# shkabara_motherboard.net
KiCad netlist of a schematic drawn in Altium Designer
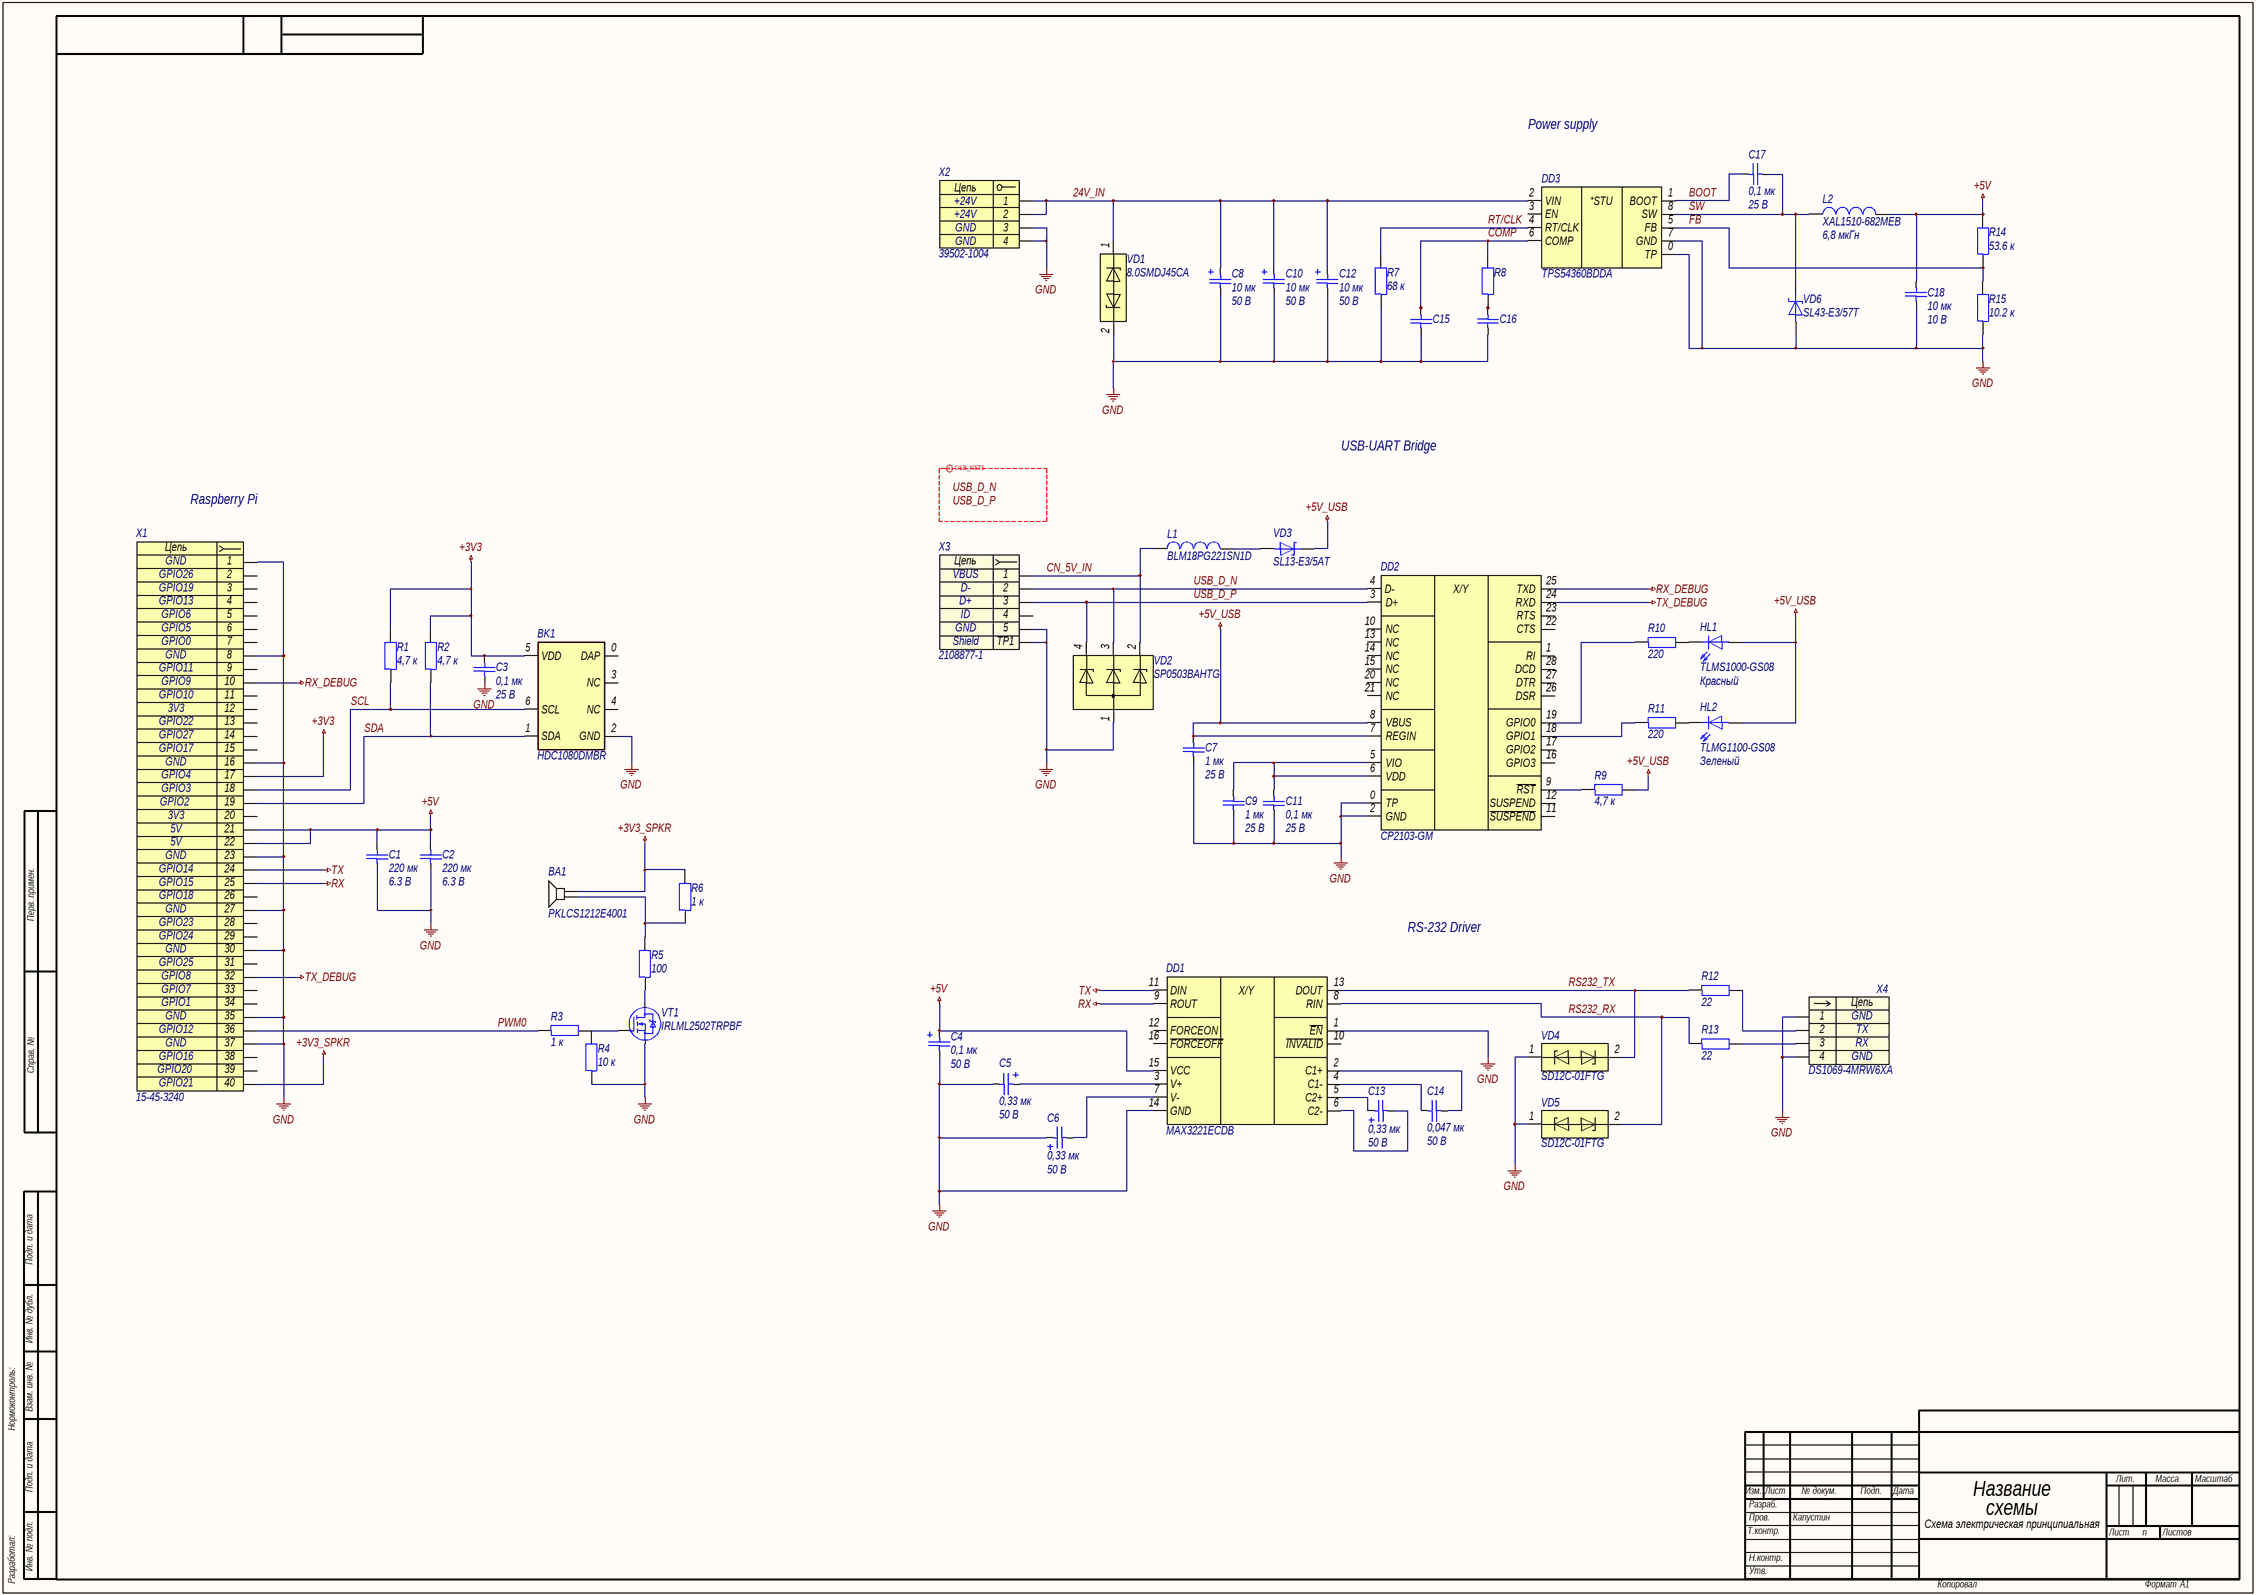
[diagram p0: shkabara_motherboard.SchDoc]

(export (version "E")
  (design (tool "Eeschema 10.0.6"))
  (components
    (comp (ref "BA1")
      (value "PKLCS1212E4001")
      (footprint "PKLCS1212E4001")
      (description "Piezoelectric Sounders External Drive SMD Type")
      (libsource (lib "PKLCS1212E4001") (part "PKLCS1212E4001"))
    )
    (comp (ref "BK1")
      (value "HDC1080DMBR")
      (footprint "PSON100P300X80_HS-7N")
      (description "HDC1080 Low Power, High Accuracy Digital Humidity Sensor with Temperature Sensor")
      (libsource (lib "HDC1080") (part "HDC1080"))
    )
    (comp (ref "C1")
      (value "220 мк")
      (footprint "C1210")
      (description "=Описание")
      (fields (field (name "НАПРЯЖЕНИЕ") "6.3 В"))
      (libsource (lib "Database_Students") (part "CAPACITOR-NONPOLAR"))
    )
    (comp (ref "C2")
      (value "220 мк")
      (footprint "C1210")
      (description "=Описание")
      (fields (field (name "НАПРЯЖЕНИЕ") "6.3 В"))
      (libsource (lib "Database_Students") (part "CAPACITOR-NONPOLAR"))
    )
    (comp (ref "C3")
      (value "0,1 мк")
      (footprint "C0402")
      (description "=Описание")
      (fields (field (name "НАПРЯЖЕНИЕ") "25 В"))
      (libsource (lib "Database_Students") (part "CAPACITOR-NONPOLAR"))
    )
    (comp (ref "C4")
      (value "0,1 мк")
      (footprint "C3216-18")
      (description "=Описание")
      (fields (field (name "НАПРЯЖЕНИЕ") "50 В"))
      (libsource (lib "Database_Students") (part "CAPACITOR-POLAR"))
    )
    (comp (ref "C5")
      (value "0,33 мк")
      (footprint "C3528-21")
      (description "=Описание")
      (fields (field (name "НАПРЯЖЕНИЕ") "50 В"))
      (libsource (lib "Database_Students") (part "CAPACITOR-POLAR"))
    )
    (comp (ref "C6")
      (value "0,33 мк")
      (footprint "C3528-21")
      (description "=Описание")
      (fields (field (name "НАПРЯЖЕНИЕ") "50 В"))
      (libsource (lib "Database_Students") (part "CAPACITOR-POLAR"))
    )
    (comp (ref "C7")
      (value "1 мк")
      (footprint "C0603")
      (description "=Описание")
      (fields (field (name "НАПРЯЖЕНИЕ") "25 В"))
      (libsource (lib "Database_Students") (part "CAPACITOR-NONPOLAR"))
    )
    (comp (ref "C8")
      (value "10 мк")
      (footprint "C7343-43")
      (description "=Описание")
      (fields (field (name "НАПРЯЖЕНИЕ") "50 В"))
      (libsource (lib "Database_Students") (part "CAPACITOR-POLAR"))
    )
    (comp (ref "C9")
      (value "1 мк")
      (footprint "C0603")
      (description "=Описание")
      (fields (field (name "НАПРЯЖЕНИЕ") "25 В"))
      (libsource (lib "Database_Students") (part "CAPACITOR-NONPOLAR"))
    )
    (comp (ref "C10")
      (value "10 мк")
      (footprint "C7343-43")
      (description "=Описание")
      (fields (field (name "НАПРЯЖЕНИЕ") "50 В"))
      (libsource (lib "Database_Students") (part "CAPACITOR-POLAR"))
    )
    (comp (ref "C11")
      (value "0,1 мк")
      (footprint "C0603")
      (description "=Описание")
      (fields (field (name "НАПРЯЖЕНИЕ") "25 В"))
      (libsource (lib "Database_Students") (part "CAPACITOR-NONPOLAR"))
    )
    (comp (ref "C12")
      (value "10 мк")
      (footprint "C7343-43")
      (description "=Описание")
      (fields (field (name "НАПРЯЖЕНИЕ") "50 В"))
      (libsource (lib "Database_Students") (part "CAPACITOR-POLAR"))
    )
    (comp (ref "C13")
      (value "0,33 мк")
      (footprint "C3528-21")
      (description "=Описание")
      (fields (field (name "НАПРЯЖЕНИЕ") "50 В"))
      (libsource (lib "Database_Students") (part "CAPACITOR-POLAR"))
    )
    (comp (ref "C14")
      (value "0,047 мк")
      (footprint "C0603")
      (description "=Описание")
      (fields (field (name "НАПРЯЖЕНИЕ") "50 В"))
      (libsource (lib "Database_Students") (part "CAPACITOR-NONPOLAR"))
    )
    (comp (ref "C15")
      (value "1000")
      (footprint "C0603")
      (description "=Описание")
      (libsource (lib "Database_Students") (part "CAPACITOR-NONPOLAR"))
    )
    (comp (ref "C16")
      (value "0,01 мк")
      (footprint "C0603")
      (description "=Описание")
      (libsource (lib "Database_Students") (part "CAPACITOR-NONPOLAR"))
    )
    (comp (ref "C17")
      (value "0,1 мк")
      (footprint "C0402")
      (description "=Описание")
      (fields (field (name "НАПРЯЖЕНИЕ") "25 В"))
      (libsource (lib "Database_Students") (part "CAPACITOR-NONPOLAR"))
    )
    (comp (ref "C18")
      (value "10 мк")
      (footprint "C0805")
      (description "=Описание")
      (fields (field (name "НАПРЯЖЕНИЕ") "10 В"))
      (libsource (lib "Database_Students") (part "CAPACITOR-NONPOLAR"))
    )
    (comp (ref "DD1")
      (value "MAX3221ECDB")
      (footprint "SSOP-16-P65-620X530X200-L75X30")
      (description "=Описание")
      (libsource (lib "Database_Students") (part "MAX3221ECDB"))
    )
    (comp (ref "DD2")
      (value "CP2103-GM")
      (footprint "QFN-28-P50-500X500X100-L55X25-T315X315")
      (description "=Описание")
      (libsource (lib "Database_Students") (part "CP2103-GM"))
    )
    (comp (ref "DD3")
      (value "TPS54360BDDA")
      (footprint "HSOIC-8-P127-490X390X170-L84X41-T310X240")
      (description "=Описание")
      (libsource (lib "Database_Students") (part "TPS54360BDDA"))
    )
    (comp (ref "HL1")
      (value "TLMS1000-GS08")
      (footprint "HL0603")
      (description "=Описание")
      (fields (field (name "ЦВЕТ") "Красный"))
      (libsource (lib "Database_Students") (part "LED-COMMON"))
    )
    (comp (ref "HL2")
      (value "TLMG1100-GS08")
      (footprint "HL0603")
      (description "=Описание")
      (fields (field (name "ЦВЕТ") "Зеленый"))
      (libsource (lib "Database_Students") (part "LED-COMMON"))
    )
    (comp (ref "L1")
      (value "BLM18PG221SN1D")
      (footprint "BLM-2-0603")
      (description "=Описание")
      (libsource (lib "Database_Students") (part "FERRITE-BEAD"))
    )
    (comp (ref "L2")
      (value "XAL1510-682MEB")
      (footprint "XAL-2-1620X1520X1000")
      (description "=Описание")
      (fields (field (name "ИНДУКТИВНОСТЬ") "6,8 мкГн"))
      (libsource (lib "Database_Students") (part "INDUCTOR-COMMON"))
    )
    (comp (ref "R1")
      (value "4,7 к")
      (footprint "R0603")
      (description "=Описание")
      (libsource (lib "Database_Students") (part "RESISTOR-COMMON"))
    )
    (comp (ref "R2")
      (value "4,7 к")
      (footprint "R0603")
      (description "=Описание")
      (libsource (lib "Database_Students") (part "RESISTOR-COMMON"))
    )
    (comp (ref "R3")
      (value "1 к")
      (footprint "R0603")
      (description "=Описание")
      (libsource (lib "Database_Students") (part "RESISTOR-COMMON"))
    )
    (comp (ref "R4")
      (value "10 к")
      (footprint "R0603")
      (description "=Описание")
      (libsource (lib "Database_Students") (part "RESISTOR-COMMON"))
    )
    (comp (ref "R5")
      (value "100")
      (footprint "R0603")
      (description "=Описание")
      (libsource (lib "Database_Students") (part "RESISTOR-COMMON"))
    )
    (comp (ref "R6")
      (value "1 к")
      (footprint "R0603")
      (description "=Описание")
      (libsource (lib "Database_Students") (part "RESISTOR-COMMON"))
    )
    (comp (ref "R7")
      (value "68 к")
      (footprint "R0603")
      (description "=Описание")
      (libsource (lib "Database_Students") (part "RESISTOR-COMMON"))
    )
    (comp (ref "R8")
      (value "3,3 к")
      (footprint "R0603")
      (description "=Описание")
      (libsource (lib "Database_Students") (part "RESISTOR-COMMON"))
    )
    (comp (ref "R9")
      (value "4,7 к")
      (footprint "R0603")
      (description "=Описание")
      (libsource (lib "Database_Students") (part "RESISTOR-COMMON"))
    )
    (comp (ref "R10")
      (value "220")
      (footprint "R0603")
      (description "=Описание")
      (libsource (lib "Database_Students") (part "RESISTOR-COMMON"))
    )
    (comp (ref "R11")
      (value "220")
      (footprint "R0603")
      (description "=Описание")
      (libsource (lib "Database_Students") (part "RESISTOR-COMMON"))
    )
    (comp (ref "R12")
      (value "22")
      (footprint "R0603")
      (description "=Описание")
      (libsource (lib "Database_Students") (part "RESISTOR-COMMON"))
    )
    (comp (ref "R13")
      (value "22")
      (footprint "R0603")
      (description "=Описание")
      (libsource (lib "Database_Students") (part "RESISTOR-COMMON"))
    )
    (comp (ref "R14")
      (value "53.6 к")
      (footprint "R1218")
      (description "=Описание")
      (libsource (lib "Database_Students") (part "RESISTOR-COMMON"))
    )
    (comp (ref "R15")
      (value "10.2 к")
      (footprint "R1218")
      (description "=Описание")
      (libsource (lib "Database_Students") (part "RESISTOR-COMMON"))
    )
    (comp (ref "VD1")
      (value "8.0SMDJ45CA")
      (footprint "DO-214AB-790X590X262")
      (description "=Описание")
      (libsource (lib "") (part "ZENER-BI-DIRECTIONAL_1"))
    )
    (comp (ref "VD2")
      (value "SP0503BAHTG")
      (footprint "SOT-143-4-P190-292X237X122")
      (description "=Описание")
      (libsource (lib "Database_Students") (part "SP0503BAHTG"))
    )
    (comp (ref "VD3")
      (value "SL13-E3/5AT")
      (footprint "DO-214AC-510X270X229")
      (description "=Описание")
      (libsource (lib "Database_Students") (part "DIODE-SCHOTTKY"))
    )
    (comp (ref "VD4")
      (value "SD12C-01FTG")
      (footprint "SOD-323-257X130X114")
      (description "=Описание")
      (libsource (lib "Database_Students") (part "ZENER-BI-DIRECTIONAL"))
    )
    (comp (ref "VD5")
      (value "SD12C-01FTG")
      (footprint "SOD-323-257X130X114")
      (description "=Описание")
      (libsource (lib "Database_Students") (part "ZENER-BI-DIRECTIONAL"))
    )
    (comp (ref "VD6")
      (value "SL43-E3/57T")
      (footprint "DO-214AB-790X590X262")
      (description "=Описание")
      (libsource (lib "Database_Students") (part "DIODE-SCHOTTKY"))
    )
    (comp (ref "VT1")
      (value "IRLML2502TRPBF")
      (footprint "SOT-23-3-P95-292X237X112")
      (description "=Описание")
      (libsource (lib "Database_Students") (part "MOSFET-N-DIODE-SCHOTTKY"))
    )
    (comp (ref "X1")
      (value "15-45-3240")
      (footprint "15-45-3240")
      (description "=Описание")
      (libsource (lib "Database_Students") (part "HEADER-40-SCT"))
    )
    (comp (ref "X2")
      (value "39502-1004")
      (footprint "39502-1004")
      (description "=Описание")
      (libsource (lib "Database_Students") (part "HEADER-4-TRM"))
    )
    (comp (ref "X3")
      (value "2108877-1")
      (footprint "2108877-1")
      (description "=Описание")
      (libsource (lib "Database_Students") (part "HEADER-5-TP1-SCT"))
    )
    (comp (ref "X4")
      (value "DS1069-4MRW6XA")
      (footprint "DS1069-4MRW6XA")
      (description "=Описание")
      (libsource (lib "Database_Students") (part "HEADER-4-PLG"))
    )
  )
  (nets
    (net (code "1") (name "+3V3") (class "Default")
      (node (ref "BK1") (pin "5") (pinfunction "VDD_5") (pintype "passive"))
      (node (ref "C3") (pin "1") (pinfunction "1_1") (pintype "passive"))
      (node (ref "R1") (pin "2") (pinfunction "2_2") (pintype "passive"))
      (node (ref "R2") (pin "2") (pinfunction "2_2") (pintype "passive"))
      (node (ref "X1") (pin "17") (pinfunction "17_17") (pintype "passive"))
    )
    (net (code "2") (name "+3V3_SPKR") (class "Default")
      (node (ref "BA1") (pin "2") (pinfunction "2_2") (pintype "passive"))
      (node (ref "R6") (pin "2") (pinfunction "2_2") (pintype "passive"))
      (node (ref "X1") (pin "40") (pinfunction "40_40") (pintype "passive"))
    )
    (net (code "3") (name "+5V") (class "Default")
      (node (ref "C1") (pin "1") (pinfunction "1_1") (pintype "passive"))
      (node (ref "C18") (pin "1") (pinfunction "1_1") (pintype "passive"))
      (node (ref "C2") (pin "1") (pinfunction "1_1") (pintype "passive"))
      (node (ref "C4") (pin "1") (pinfunction "1_1") (pintype "passive"))
      (node (ref "DD1") (pin "15") (pinfunction "VCC_15") (pintype "passive"))
      (node (ref "L2") (pin "2") (pinfunction "2_2") (pintype "passive"))
      (node (ref "R14") (pin "2") (pinfunction "2_2") (pintype "passive"))
      (node (ref "X1") (pin "21") (pinfunction "21_21") (pintype "passive"))
      (node (ref "X1") (pin "22") (pinfunction "22_22") (pintype "passive"))
    )
    (net (code "4") (name "+5V_USB") (class "Default")
      (node (ref "C7") (pin "1") (pinfunction "1_1") (pintype "passive"))
      (node (ref "DD2") (pin "7") (pinfunction "REGIN_7") (pintype "passive"))
      (node (ref "DD2") (pin "8") (pinfunction "VBUS_8") (pintype "passive"))
      (node (ref "HL1") (pin "2") (pinfunction "2_2") (pintype "passive"))
      (node (ref "HL2") (pin "2") (pinfunction "2_2") (pintype "passive"))
      (node (ref "R9") (pin "2") (pinfunction "2_2") (pintype "passive"))
      (node (ref "VD3") (pin "1") (pinfunction "1_1") (pintype "passive"))
    )
    (net (code "5") (name "/24V_IN") (class "Default")
      (node (ref "C10") (pin "1") (pinfunction "1_1") (pintype "passive"))
      (node (ref "C12") (pin "1") (pinfunction "1_1") (pintype "passive"))
      (node (ref "C8") (pin "1") (pinfunction "1_1") (pintype "passive"))
      (node (ref "DD3") (pin "2") (pinfunction "VIN_2") (pintype "passive"))
      (node (ref "VD1") (pin "1") (pinfunction "1_1") (pintype "passive"))
      (node (ref "X2") (pin "1") (pinfunction "1_1") (pintype "passive"))
      (node (ref "X2") (pin "2") (pinfunction "2_2") (pintype "passive"))
    )
    (net (code "6") (name "/BOOT") (class "Default")
      (node (ref "C17") (pin "2") (pinfunction "2_2") (pintype "passive"))
      (node (ref "DD3") (pin "1") (pinfunction "BOOT_1") (pintype "passive"))
    )
    (net (code "7") (name "/CN_5V_IN") (class "Default")
      (node (ref "L1") (pin "1") (pinfunction "1_1") (pintype "passive"))
      (node (ref "VD2") (pin "2") (pinfunction "2_2") (pintype "passive"))
      (node (ref "X3") (pin "1") (pinfunction "1_1") (pintype "passive"))
    )
    (net (code "8") (name "/COMP") (class "Default")
      (node (ref "C15") (pin "1") (pinfunction "1_1") (pintype "passive"))
      (node (ref "DD3") (pin "6") (pinfunction "COMP_6") (pintype "passive"))
      (node (ref "R8") (pin "2") (pinfunction "2_2") (pintype "passive"))
    )
    (net (code "9") (name "/FB") (class "Default")
      (node (ref "DD3") (pin "5") (pinfunction "FB_5") (pintype "passive"))
      (node (ref "R14") (pin "1") (pinfunction "1_1") (pintype "passive"))
      (node (ref "R15") (pin "2") (pinfunction "2_2") (pintype "passive"))
    )
    (net (code "10") (name "/PWM0") (class "Default")
      (node (ref "R3") (pin "1") (pinfunction "1_1") (pintype "passive"))
      (node (ref "X1") (pin "36") (pinfunction "36_36") (pintype "passive"))
    )
    (net (code "11") (name "/RS232_RX") (class "Default")
      (node (ref "DD1") (pin "8") (pinfunction "RIN_8") (pintype "passive"))
      (node (ref "R13") (pin "1") (pinfunction "1_1") (pintype "passive"))
      (node (ref "VD5") (pin "2") (pinfunction "2_2") (pintype "passive"))
    )
    (net (code "12") (name "/RS232_TX") (class "Default")
      (node (ref "DD1") (pin "13") (pinfunction "DOUT_13") (pintype "passive"))
      (node (ref "R12") (pin "1") (pinfunction "1_1") (pintype "passive"))
      (node (ref "VD4") (pin "2") (pinfunction "2_2") (pintype "passive"))
    )
    (net (code "13") (name "/RT{slash}CLK") (class "Default")
      (node (ref "DD3") (pin "4") (pinfunction "RT/CLK_4") (pintype "passive"))
      (node (ref "R7") (pin "2") (pinfunction "2_2") (pintype "passive"))
    )
    (net (code "14") (name "/SCL") (class "Default")
      (node (ref "BK1") (pin "6") (pinfunction "SCL_6") (pintype "passive"))
      (node (ref "R1") (pin "1") (pinfunction "1_1") (pintype "passive"))
      (node (ref "X1") (pin "18") (pinfunction "18_18") (pintype "passive"))
    )
    (net (code "15") (name "/SDA") (class "Default")
      (node (ref "BK1") (pin "1") (pinfunction "SDA_1") (pintype "passive"))
      (node (ref "R2") (pin "1") (pinfunction "1_1") (pintype "passive"))
      (node (ref "X1") (pin "19") (pinfunction "19_19") (pintype "passive"))
    )
    (net (code "16") (name "/SW") (class "Default")
      (node (ref "C17") (pin "1") (pinfunction "1_1") (pintype "passive"))
      (node (ref "DD3") (pin "8") (pinfunction "SW_8") (pintype "passive"))
      (node (ref "L2") (pin "1") (pinfunction "1_1") (pintype "passive"))
      (node (ref "VD6") (pin "1") (pinfunction "1_1") (pintype "passive"))
    )
    (net (code "17") (name "/USB_D_N") (class "Default")
      (node (ref "DD2") (pin "4") (pinfunction "D-_4") (pintype "passive"))
      (node (ref "VD2") (pin "3") (pinfunction "3_3") (pintype "passive"))
      (node (ref "X3") (pin "2") (pinfunction "2_2") (pintype "passive"))
    )
    (net (code "18") (name "/USB_D_P") (class "Default")
      (node (ref "DD2") (pin "3") (pinfunction "D+_3") (pintype "passive"))
      (node (ref "VD2") (pin "4") (pinfunction "4_4") (pintype "passive"))
      (node (ref "X3") (pin "3") (pinfunction "3_3") (pintype "passive"))
    )
    (net (code "19") (name "GND") (class "Default")
      (node (ref "BK1") (pin "2") (pinfunction "GND_2") (pintype "passive"))
      (node (ref "C1") (pin "2") (pinfunction "2_2") (pintype "passive"))
      (node (ref "C10") (pin "2") (pinfunction "2_2") (pintype "passive"))
      (node (ref "C11") (pin "2") (pinfunction "2_2") (pintype "passive"))
      (node (ref "C12") (pin "2") (pinfunction "2_2") (pintype "passive"))
      (node (ref "C15") (pin "2") (pinfunction "2_2") (pintype "passive"))
      (node (ref "C16") (pin "1") (pinfunction "1_1") (pintype "passive"))
      (node (ref "C18") (pin "2") (pinfunction "2_2") (pintype "passive"))
      (node (ref "C2") (pin "2") (pinfunction "2_2") (pintype "passive"))
      (node (ref "C3") (pin "2") (pinfunction "2_2") (pintype "passive"))
      (node (ref "C4") (pin "2") (pinfunction "2_2") (pintype "passive"))
      (node (ref "C5") (pin "2") (pinfunction "2_2") (pintype "passive"))
      (node (ref "C6") (pin "1") (pinfunction "1_1") (pintype "passive"))
      (node (ref "C7") (pin "2") (pinfunction "2_2") (pintype "passive"))
      (node (ref "C8") (pin "2") (pinfunction "2_2") (pintype "passive"))
      (node (ref "C9") (pin "1") (pinfunction "1_1") (pintype "passive"))
      (node (ref "DD1") (pin "1") (pinfunction "~{EN}_1") (pintype "passive"))
      (node (ref "DD1") (pin "14") (pinfunction "GND_14") (pintype "passive"))
      (node (ref "DD2") (pin "0") (pinfunction "TP_0") (pintype "passive"))
      (node (ref "DD2") (pin "2") (pinfunction "GND_2") (pintype "passive"))
      (node (ref "DD3") (pin "0") (pinfunction "TP_0") (pintype "passive"))
      (node (ref "DD3") (pin "7") (pinfunction "GND_7") (pintype "passive"))
      (node (ref "R15") (pin "1") (pinfunction "1_1") (pintype "passive"))
      (node (ref "R4") (pin "1") (pinfunction "1_1") (pintype "passive"))
      (node (ref "R7") (pin "1") (pinfunction "1_1") (pintype "passive"))
      (node (ref "VD1") (pin "2") (pinfunction "2_2") (pintype "passive"))
      (node (ref "VD2") (pin "1") (pinfunction "1_1") (pintype "passive"))
      (node (ref "VD4") (pin "1") (pinfunction "1_1") (pintype "passive"))
      (node (ref "VD5") (pin "1") (pinfunction "1_1") (pintype "passive"))
      (node (ref "VD6") (pin "2") (pinfunction "2_2") (pintype "passive"))
      (node (ref "VT1") (pin "S") (pinfunction "S_S") (pintype "passive"))
      (node (ref "X1") (pin "1") (pinfunction "1_1") (pintype "passive"))
      (node (ref "X1") (pin "16") (pinfunction "16_16") (pintype "passive"))
      (node (ref "X1") (pin "23") (pinfunction "23_23") (pintype "passive"))
      (node (ref "X1") (pin "27") (pinfunction "27_27") (pintype "passive"))
      (node (ref "X1") (pin "30") (pinfunction "30_30") (pintype "passive"))
      (node (ref "X1") (pin "35") (pinfunction "35_35") (pintype "passive"))
      (node (ref "X1") (pin "37") (pinfunction "37_37") (pintype "passive"))
      (node (ref "X1") (pin "8") (pinfunction "8_8") (pintype "passive"))
      (node (ref "X2") (pin "3") (pinfunction "3_3") (pintype "passive"))
      (node (ref "X2") (pin "4") (pinfunction "4_4") (pintype "passive"))
      (node (ref "X3") (pin "5") (pinfunction "5_5") (pintype "passive"))
      (node (ref "X3") (pin "TP1") (pinfunction "TP1_TP1") (pintype "passive"))
      (node (ref "X4") (pin "1") (pinfunction "1_1") (pintype "passive"))
      (node (ref "X4") (pin "4") (pinfunction "4_4") (pintype "passive"))
    )
    (net (code "20") (name "Net-(BA1-Pad1)") (class "Default")
      (node (ref "BA1") (pin "1") (pinfunction "1_1") (pintype "passive"))
      (node (ref "R5") (pin "2") (pinfunction "2_2") (pintype "passive"))
      (node (ref "R6") (pin "1") (pinfunction "1_1") (pintype "passive"))
    )
    (net (code "21") (name "Net-(C16-Pad2)") (class "Default")
      (node (ref "C16") (pin "2") (pinfunction "2_2") (pintype "passive"))
      (node (ref "R8") (pin "1") (pinfunction "1_1") (pintype "passive"))
    )
    (net (code "22") (name "Net-(DD1-C1+)") (class "Default")
      (node (ref "C14") (pin "2") (pinfunction "2_2") (pintype "passive"))
      (node (ref "DD1") (pin "2") (pinfunction "C1+_2") (pintype "passive"))
    )
    (net (code "23") (name "Net-(DD1-C1-)") (class "Default")
      (node (ref "C14") (pin "1") (pinfunction "1_1") (pintype "passive"))
      (node (ref "DD1") (pin "4") (pinfunction "C1-_4") (pintype "passive"))
    )
    (net (code "24") (name "Net-(DD1-C2+)") (class "Default")
      (node (ref "C13") (pin "1") (pinfunction "1_1") (pintype "passive"))
      (node (ref "DD1") (pin "5") (pinfunction "C2+_5") (pintype "passive"))
    )
    (net (code "25") (name "Net-(DD1-C2-)") (class "Default")
      (node (ref "C13") (pin "2") (pinfunction "2_2") (pintype "passive"))
      (node (ref "DD1") (pin "6") (pinfunction "C2-_6") (pintype "passive"))
    )
    (net (code "26") (name "Net-(DD1-V+)") (class "Default")
      (node (ref "C5") (pin "1") (pinfunction "1_1") (pintype "passive"))
      (node (ref "DD1") (pin "3") (pinfunction "V+_3") (pintype "passive"))
    )
    (net (code "27") (name "Net-(DD1-V-)") (class "Default")
      (node (ref "C6") (pin "2") (pinfunction "2_2") (pintype "passive"))
      (node (ref "DD1") (pin "7") (pinfunction "V-_7") (pintype "passive"))
    )
    (net (code "28") (name "Net-(DD2-GPIO0)") (class "Default")
      (node (ref "DD2") (pin "19") (pinfunction "GPIO0_19") (pintype "passive"))
      (node (ref "R10") (pin "1") (pinfunction "1_1") (pintype "passive"))
    )
    (net (code "29") (name "Net-(DD2-GPIO1)") (class "Default")
      (node (ref "DD2") (pin "18") (pinfunction "GPIO1_18") (pintype "passive"))
      (node (ref "R11") (pin "1") (pinfunction "1_1") (pintype "passive"))
    )
    (net (code "30") (name "Net-(DD2-VDD)") (class "Default")
      (node (ref "C11") (pin "1") (pinfunction "1_1") (pintype "passive"))
      (node (ref "C9") (pin "2") (pinfunction "2_2") (pintype "passive"))
      (node (ref "DD2") (pin "5") (pinfunction "VIO_5") (pintype "passive"))
      (node (ref "DD2") (pin "6") (pinfunction "VDD_6") (pintype "passive"))
    )
    (net (code "31") (name "Net-(DD2-~{RST})") (class "Default")
      (node (ref "DD2") (pin "9") (pinfunction "~{RST}_9") (pintype "passive"))
      (node (ref "R9") (pin "1") (pinfunction "1_1") (pintype "passive"))
    )
    (net (code "32") (name "Net-(HL1-Pad1)") (class "Default")
      (node (ref "HL1") (pin "1") (pinfunction "1_1") (pintype "passive"))
      (node (ref "R10") (pin "2") (pinfunction "2_2") (pintype "passive"))
    )
    (net (code "33") (name "Net-(HL2-Pad1)") (class "Default")
      (node (ref "HL2") (pin "1") (pinfunction "1_1") (pintype "passive"))
      (node (ref "R11") (pin "2") (pinfunction "2_2") (pintype "passive"))
    )
    (net (code "34") (name "Net-(L1-Pad2)") (class "Default")
      (node (ref "L1") (pin "2") (pinfunction "2_2") (pintype "passive"))
      (node (ref "VD3") (pin "2") (pinfunction "2_2") (pintype "passive"))
    )
    (net (code "35") (name "Net-(R3-Pad2)") (class "Default")
      (node (ref "R3") (pin "2") (pinfunction "2_2") (pintype "passive"))
      (node (ref "R4") (pin "2") (pinfunction "2_2") (pintype "passive"))
      (node (ref "VT1") (pin "G") (pinfunction "G_G") (pintype "passive"))
    )
    (net (code "36") (name "Net-(R5-Pad1)") (class "Default")
      (node (ref "R5") (pin "1") (pinfunction "1_1") (pintype "passive"))
      (node (ref "VT1") (pin "D") (pinfunction "D_D") (pintype "passive"))
    )
    (net (code "37") (name "Net-(R12-Pad2)") (class "Default")
      (node (ref "R12") (pin "2") (pinfunction "2_2") (pintype "passive"))
      (node (ref "X4") (pin "2") (pinfunction "2_2") (pintype "passive"))
    )
    (net (code "38") (name "Net-(R13-Pad2)") (class "Default")
      (node (ref "R13") (pin "2") (pinfunction "2_2") (pintype "passive"))
      (node (ref "X4") (pin "3") (pinfunction "3_3") (pintype "passive"))
    )
    (net (code "39") (name "RX") (class "Default")
      (node (ref "DD1") (pin "9") (pinfunction "ROUT_9") (pintype "passive"))
      (node (ref "X1") (pin "25") (pinfunction "25_25") (pintype "passive"))
    )
    (net (code "40") (name "RX_DEBUG") (class "Default")
      (node (ref "DD2") (pin "25") (pinfunction "TXD_25") (pintype "passive"))
      (node (ref "X1") (pin "10") (pinfunction "10_10") (pintype "passive"))
    )
    (net (code "41") (name "TX") (class "Default")
      (node (ref "DD1") (pin "11") (pinfunction "DIN_11") (pintype "passive"))
      (node (ref "X1") (pin "24") (pinfunction "24_24") (pintype "passive"))
    )
    (net (code "42") (name "TX_DEBUG") (class "Default")
      (node (ref "DD2") (pin "24") (pinfunction "RXD_24") (pintype "passive"))
      (node (ref "X1") (pin "32") (pinfunction "32_32") (pintype "passive"))
    )
    (net (code "43") (name "unconnected-(BK1-DAP-Pad0)") (class "Default")
      (node (ref "BK1") (pin "0") (pinfunction "DAP_0") (pintype "passive"))
    )
    (net (code "44") (name "unconnected-(BK1-NC-Pad3)") (class "Default")
      (node (ref "BK1") (pin "3") (pinfunction "NC_3") (pintype "passive"))
    )
    (net (code "45") (name "unconnected-(BK1-NC-Pad4)") (class "Default")
      (node (ref "BK1") (pin "4") (pinfunction "NC_4") (pintype "passive"))
    )
    (net (code "46") (name "unconnected-(DD1-FORCEON-Pad12)") (class "Default")
      (node (ref "DD1") (pin "12") (pinfunction "FORCEON_12") (pintype "passive"))
    )
    (net (code "47") (name "unconnected-(DD1-~{FORCEOFF}-Pad16)") (class "Default")
      (node (ref "DD1") (pin "16") (pinfunction "~{FORCEOFF}_16") (pintype "passive"))
    )
    (net (code "48") (name "unconnected-(DD1-~{INVALID}-Pad10)") (class "Default")
      (node (ref "DD1") (pin "10") (pinfunction "~{INVALID}_10") (pintype "passive"))
    )
    (net (code "49") (name "unconnected-(DD2-CTS-Pad22)") (class "Default")
      (node (ref "DD2") (pin "22") (pinfunction "CTS_22") (pintype "passive"))
    )
    (net (code "50") (name "unconnected-(DD2-DCD-Pad28)") (class "Default")
      (node (ref "DD2") (pin "28") (pinfunction "DCD_28") (pintype "passive"))
    )
    (net (code "51") (name "unconnected-(DD2-DSR-Pad26)") (class "Default")
      (node (ref "DD2") (pin "26") (pinfunction "DSR_26") (pintype "passive"))
    )
    (net (code "52") (name "unconnected-(DD2-DTR-Pad27)") (class "Default")
      (node (ref "DD2") (pin "27") (pinfunction "DTR_27") (pintype "passive"))
    )
    (net (code "53") (name "unconnected-(DD2-GPIO2-Pad17)") (class "Default")
      (node (ref "DD2") (pin "17") (pinfunction "GPIO2_17") (pintype "passive"))
    )
    (net (code "54") (name "unconnected-(DD2-GPIO3-Pad16)") (class "Default")
      (node (ref "DD2") (pin "16") (pinfunction "GPIO3_16") (pintype "passive"))
    )
    (net (code "55") (name "unconnected-(DD2-NC-Pad10)") (class "Default")
      (node (ref "DD2") (pin "10") (pinfunction "NC_10") (pintype "passive"))
    )
    (net (code "56") (name "unconnected-(DD2-NC-Pad13)") (class "Default")
      (node (ref "DD2") (pin "13") (pinfunction "NC_13") (pintype "passive"))
    )
    (net (code "57") (name "unconnected-(DD2-NC-Pad14)") (class "Default")
      (node (ref "DD2") (pin "14") (pinfunction "NC_14") (pintype "passive"))
    )
    (net (code "58") (name "unconnected-(DD2-NC-Pad15)") (class "Default")
      (node (ref "DD2") (pin "15") (pinfunction "NC_15") (pintype "passive"))
    )
    (net (code "59") (name "unconnected-(DD2-NC-Pad20)") (class "Default")
      (node (ref "DD2") (pin "20") (pinfunction "NC_20") (pintype "passive"))
    )
    (net (code "60") (name "unconnected-(DD2-NC-Pad21)") (class "Default")
      (node (ref "DD2") (pin "21") (pinfunction "NC_21") (pintype "passive"))
    )
    (net (code "61") (name "unconnected-(DD2-RI-Pad1)") (class "Default")
      (node (ref "DD2") (pin "1") (pinfunction "RI_1") (pintype "passive"))
    )
    (net (code "62") (name "unconnected-(DD2-RTS-Pad23)") (class "Default")
      (node (ref "DD2") (pin "23") (pinfunction "RTS_23") (pintype "passive"))
    )
    (net (code "63") (name "unconnected-(DD2-SUSPEND-Pad12)") (class "Default")
      (node (ref "DD2") (pin "12") (pinfunction "SUSPEND_12") (pintype "passive"))
    )
    (net (code "64") (name "unconnected-(DD2-~{SUSPEND}-Pad11)") (class "Default")
      (node (ref "DD2") (pin "11") (pinfunction "~{SUSPEND}_11") (pintype "passive"))
    )
    (net (code "65") (name "unconnected-(DD3-EN-Pad3)") (class "Default")
      (node (ref "DD3") (pin "3") (pinfunction "EN_3") (pintype "passive"))
    )
    (net (code "66") (name "unconnected-(X1-Pad2)") (class "Default")
      (node (ref "X1") (pin "2") (pinfunction "2_2") (pintype "passive"))
    )
    (net (code "67") (name "unconnected-(X1-Pad3)") (class "Default")
      (node (ref "X1") (pin "3") (pinfunction "3_3") (pintype "passive"))
    )
    (net (code "68") (name "unconnected-(X1-Pad4)") (class "Default")
      (node (ref "X1") (pin "4") (pinfunction "4_4") (pintype "passive"))
    )
    (net (code "69") (name "unconnected-(X1-Pad5)") (class "Default")
      (node (ref "X1") (pin "5") (pinfunction "5_5") (pintype "passive"))
    )
    (net (code "70") (name "unconnected-(X1-Pad6)") (class "Default")
      (node (ref "X1") (pin "6") (pinfunction "6_6") (pintype "passive"))
    )
    (net (code "71") (name "unconnected-(X1-Pad7)") (class "Default")
      (node (ref "X1") (pin "7") (pinfunction "7_7") (pintype "passive"))
    )
    (net (code "72") (name "unconnected-(X1-Pad9)") (class "Default")
      (node (ref "X1") (pin "9") (pinfunction "9_9") (pintype "passive"))
    )
    (net (code "73") (name "unconnected-(X1-Pad11)") (class "Default")
      (node (ref "X1") (pin "11") (pinfunction "11_11") (pintype "passive"))
    )
    (net (code "74") (name "unconnected-(X1-Pad12)") (class "Default")
      (node (ref "X1") (pin "12") (pinfunction "12_12") (pintype "passive"))
    )
    (net (code "75") (name "unconnected-(X1-Pad13)") (class "Default")
      (node (ref "X1") (pin "13") (pinfunction "13_13") (pintype "passive"))
    )
    (net (code "76") (name "unconnected-(X1-Pad14)") (class "Default")
      (node (ref "X1") (pin "14") (pinfunction "14_14") (pintype "passive"))
    )
    (net (code "77") (name "unconnected-(X1-Pad15)") (class "Default")
      (node (ref "X1") (pin "15") (pinfunction "15_15") (pintype "passive"))
    )
    (net (code "78") (name "unconnected-(X1-Pad20)") (class "Default")
      (node (ref "X1") (pin "20") (pinfunction "20_20") (pintype "passive"))
    )
    (net (code "79") (name "unconnected-(X1-Pad26)") (class "Default")
      (node (ref "X1") (pin "26") (pinfunction "26_26") (pintype "passive"))
    )
    (net (code "80") (name "unconnected-(X1-Pad28)") (class "Default")
      (node (ref "X1") (pin "28") (pinfunction "28_28") (pintype "passive"))
    )
    (net (code "81") (name "unconnected-(X1-Pad29)") (class "Default")
      (node (ref "X1") (pin "29") (pinfunction "29_29") (pintype "passive"))
    )
    (net (code "82") (name "unconnected-(X1-Pad31)") (class "Default")
      (node (ref "X1") (pin "31") (pinfunction "31_31") (pintype "passive"))
    )
    (net (code "83") (name "unconnected-(X1-Pad33)") (class "Default")
      (node (ref "X1") (pin "33") (pinfunction "33_33") (pintype "passive"))
    )
    (net (code "84") (name "unconnected-(X1-Pad34)") (class "Default")
      (node (ref "X1") (pin "34") (pinfunction "34_34") (pintype "passive"))
    )
    (net (code "85") (name "unconnected-(X1-Pad38)") (class "Default")
      (node (ref "X1") (pin "38") (pinfunction "38_38") (pintype "passive"))
    )
    (net (code "86") (name "unconnected-(X1-Pad39)") (class "Default")
      (node (ref "X1") (pin "39") (pinfunction "39_39") (pintype "passive"))
    )
    (net (code "87") (name "unconnected-(X3-Pad4)") (class "Default")
      (node (ref "X3") (pin "4") (pinfunction "4_4") (pintype "passive"))
    )
  )
)
